# Rauchmelder.net
KiCad netlist of a schematic drawn in EAGLE
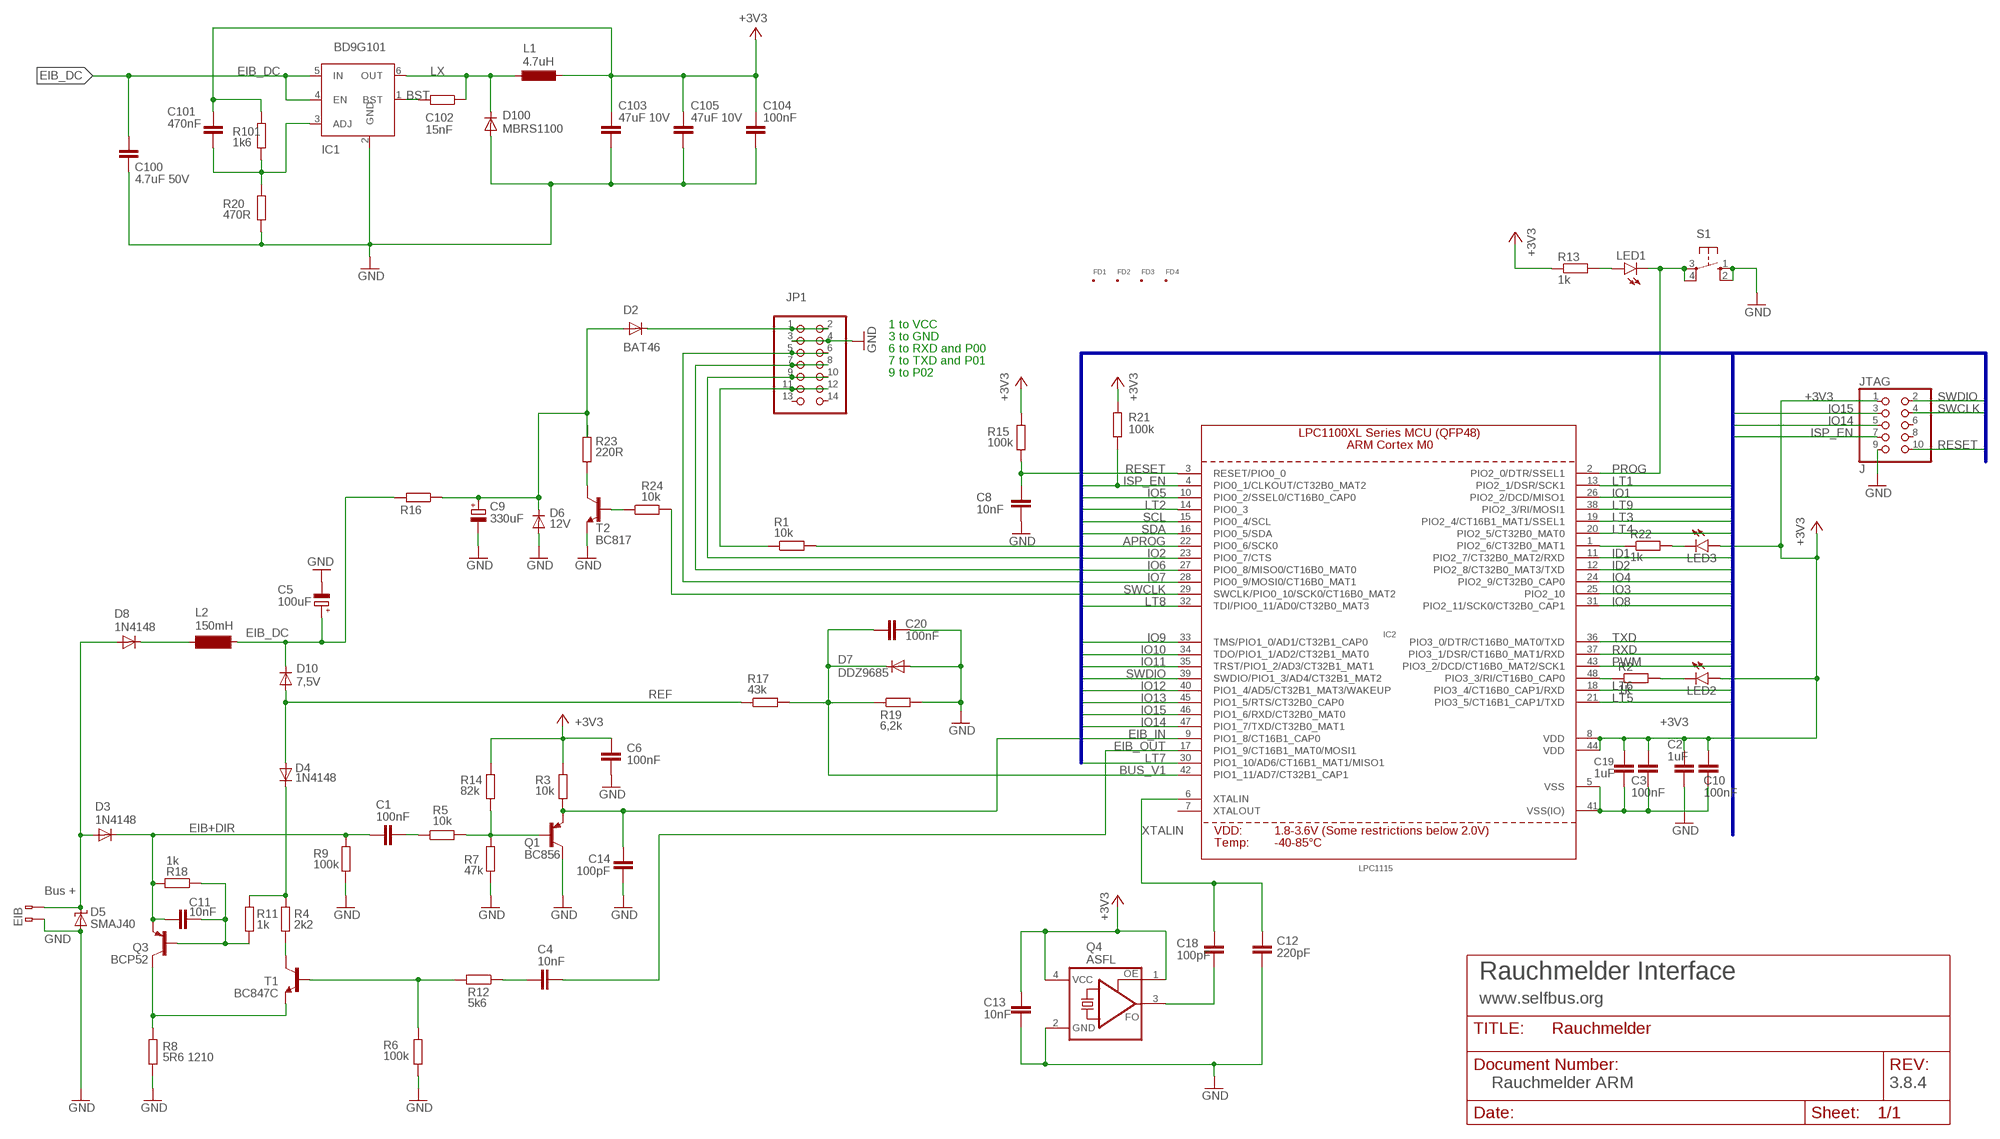
[diagram p0: schematic, sheet 1]

(export (version "E")
  (design (tool "Eeschema 10.0.6"))
  (components
    (comp (ref "C1")
      (value "100nF")
      (footprint "eagle-import:C0805")
      (libsource (lib "eagle-import") (part "C-EUC0805"))
    )
    (comp (ref "C2")
      (value "1uF")
      (footprint "eagle-import:C0805")
      (libsource (lib "eagle-import") (part "C-EUC0805"))
    )
    (comp (ref "C3")
      (value "100nF")
      (footprint "eagle-import:C0805")
      (libsource (lib "eagle-import") (part "C-EUC0805"))
    )
    (comp (ref "C4")
      (value "10nF")
      (footprint "eagle-import:C0805")
      (libsource (lib "eagle-import") (part "C-EUC0805"))
    )
    (comp (ref "C5")
      (value "100uF")
      (footprint "eagle-import:SANYO-OSCON_SMD_C6")
      (libsource (lib "eagle-import") (part "CPOL-EUSANYO_SMD_C6"))
    )
    (comp (ref "C6")
      (value "100nF")
      (footprint "eagle-import:C0805")
      (libsource (lib "eagle-import") (part "C-EUC0805"))
    )
    (comp (ref "C8")
      (value "10nF")
      (footprint "eagle-import:C0805")
      (libsource (lib "eagle-import") (part "C-EUC0805"))
    )
    (comp (ref "C9")
      (value "330uF")
      (footprint "eagle-import:E3,5-8")
      (libsource (lib "eagle-import") (part "CPOL-EUE3.5-8"))
    )
    (comp (ref "C10")
      (value "100nF")
      (footprint "eagle-import:C0805")
      (libsource (lib "eagle-import") (part "C-EUC0805"))
    )
    (comp (ref "C11")
      (value "10nF")
      (footprint "eagle-import:C0805")
      (libsource (lib "eagle-import") (part "C-EUC0805"))
    )
    (comp (ref "C12")
      (value "220pF")
      (footprint "eagle-import:C0805")
      (libsource (lib "eagle-import") (part "C-EUC0805"))
    )
    (comp (ref "C13")
      (value "10nF")
      (footprint "eagle-import:C0805")
      (libsource (lib "eagle-import") (part "C-EUC0805"))
    )
    (comp (ref "C14")
      (value "100pF")
      (footprint "eagle-import:C0805")
      (libsource (lib "eagle-import") (part "C-EUC0805"))
    )
    (comp (ref "C18")
      (value "100pF")
      (footprint "eagle-import:C0805")
      (libsource (lib "eagle-import") (part "C-EUC0805"))
    )
    (comp (ref "C19")
      (value "1uF")
      (footprint "eagle-import:C0805")
      (libsource (lib "eagle-import") (part "C-EUC0805"))
    )
    (comp (ref "C20")
      (value "100nF")
      (footprint "eagle-import:C0805")
      (libsource (lib "eagle-import") (part "C-EUC0805"))
    )
    (comp (ref "C100")
      (value "4.7uF 50V")
      (footprint "eagle-import:C0805")
      (libsource (lib "eagle-import") (part "C-EUC0805"))
    )
    (comp (ref "C101")
      (value "470nF")
      (footprint "eagle-import:C0805")
      (libsource (lib "eagle-import") (part "C-EUC0805"))
    )
    (comp (ref "C102")
      (value "15nF")
      (footprint "eagle-import:R0805")
      (libsource (lib "eagle-import") (part "R-EU_R0805"))
    )
    (comp (ref "C103")
      (value "47uF 10V")
      (footprint "eagle-import:C0805")
      (libsource (lib "eagle-import") (part "C-EUC0805"))
    )
    (comp (ref "C104")
      (value "100nF")
      (footprint "eagle-import:C0805")
      (libsource (lib "eagle-import") (part "C-EUC0805"))
    )
    (comp (ref "C105")
      (value "47uF 10V")
      (footprint "eagle-import:C0805")
      (libsource (lib "eagle-import") (part "C-EUC0805"))
    )
    (comp (ref "D2")
      (value "BAT46")
      (footprint "eagle-import:SOD-123")
      (libsource (lib "eagle-import") (part "DIODESOD-123"))
    )
    (comp (ref "D3")
      (value "1N4148")
      (footprint "eagle-import:SOD-123")
      (libsource (lib "eagle-import") (part "DIODESOD-123"))
    )
    (comp (ref "D4")
      (value "1N4148")
      (footprint "eagle-import:SOD-123")
      (libsource (lib "eagle-import") (part "DIODESOD-123"))
    )
    (comp (ref "D5")
      (value "SMAJ40")
      (footprint "eagle-import:SMBJ")
      (libsource (lib "eagle-import") (part "SUPPRESSOR-SMBJ"))
    )
    (comp (ref "D6")
      (value "12V")
      (footprint "eagle-import:SOD-123")
      (libsource (lib "eagle-import") (part "DIODESOD-123"))
    )
    (comp (ref "D7")
      (value "DDZ9685")
      (footprint "eagle-import:SOD-123")
      (libsource (lib "eagle-import") (part "DIODESOD-123"))
    )
    (comp (ref "D8")
      (value "1N4148")
      (footprint "eagle-import:SOD-123")
      (libsource (lib "eagle-import") (part "DIODESOD-123"))
    )
    (comp (ref "D10")
      (value "7,5V")
      (footprint "eagle-import:SOD-123")
      (libsource (lib "eagle-import") (part "DIODESOD-123"))
    )
    (comp (ref "D100")
      (value "MBRS1100")
      (footprint "eagle-import:SOD-123")
      (libsource (lib "eagle-import") (part "DIODESOD-123"))
    )
    (comp (ref "FD1")
      (value "FID_40MIL")
      (footprint "eagle-import:FID_040")
      (libsource (lib "eagle-import") (part "FID_40MIL"))
    )
    (comp (ref "FD2")
      (value "FID_40MIL")
      (footprint "eagle-import:FID_040")
      (libsource (lib "eagle-import") (part "FID_40MIL"))
    )
    (comp (ref "FD3")
      (value "FID_40MIL")
      (footprint "eagle-import:FID_040")
      (libsource (lib "eagle-import") (part "FID_40MIL"))
    )
    (comp (ref "FD4")
      (value "FID_40MIL")
      (footprint "eagle-import:FID_040")
      (libsource (lib "eagle-import") (part "FID_40MIL"))
    )
    (comp (ref "IC1")
      (value "BD9G101")
      (footprint "eagle-import:SOT23-6")
      (libsource (lib "eagle-import") (part "BD9G101GBD9G101G-SOT23-6"))
    )
    (comp (ref "IC2")
      (value "LPC1115")
      (footprint "eagle-import:LQFP48")
      (libsource (lib "eagle-import") (part "LPC1113/4/5_QFP48_XLSERIES"))
    )
    (comp (ref "JP1")
      (value "PINHD-2X7")
      (footprint "eagle-import:2X07")
      (libsource (lib "eagle-import") (part "PINHD-2X7"))
    )
    (comp (ref "JTAG")
      (value "J")
      (footprint "eagle-import:2X05M")
      (libsource (lib "eagle-import") (part "PINHD-2X05_2.00"))
    )
    (comp (ref "L1")
      (value "4.7uH")
      (footprint "eagle-import:L4532P")
      (libsource (lib "eagle-import") (part "L-EUL4532P"))
    )
    (comp (ref "L2")
      (value "150mH")
      (footprint "eagle-import:BS11")
      (libsource (lib "eagle-import") (part "BS11"))
    )
    (comp (ref "LED1")
      (value "LEDCHIPLED_0805")
      (footprint "eagle-import:CHIPLED_0805")
      (libsource (lib "eagle-import") (part "LEDCHIPLED_0805"))
    )
    (comp (ref "LED2")
      (value "LEDCHIPLED_0805")
      (footprint "eagle-import:CHIPLED_0805")
      (libsource (lib "eagle-import") (part "LEDCHIPLED_0805"))
    )
    (comp (ref "LED3")
      (value "LEDCHIPLED_0805")
      (footprint "eagle-import:CHIPLED_0805")
      (libsource (lib "eagle-import") (part "LEDCHIPLED_0805"))
    )
    (comp (ref "Q1")
      (value "BC856")
      (footprint "eagle-import:SOT23-BEC")
      (libsource (lib "eagle-import") (part "BC856SMDALT1"))
    )
    (comp (ref "Q3")
      (value "BCP52")
      (footprint "eagle-import:SOT223")
      (libsource (lib "eagle-import") (part "FZT753SMD"))
    )
    (comp (ref "Q4")
      (value "ASFL")
      (footprint "eagle-import:ASF")
      (fields (field (name "MPN") "ASFLM1-50.000MHZ-C-T"))
      (libsource (lib "eagle-import") (part "ASFL"))
    )
    (comp (ref "R1")
      (value "10k")
      (footprint "eagle-import:R0805")
      (libsource (lib "eagle-import") (part "R-EU_R0805"))
    )
    (comp (ref "R2")
      (value "1k")
      (footprint "eagle-import:R0805")
      (libsource (lib "eagle-import") (part "R-EU_R0805"))
    )
    (comp (ref "R3")
      (value "10k")
      (footprint "eagle-import:R0805")
      (libsource (lib "eagle-import") (part "R-EU_R0805"))
    )
    (comp (ref "R4")
      (value "2k2")
      (footprint "eagle-import:R0805")
      (libsource (lib "eagle-import") (part "R-EU_R0805"))
    )
    (comp (ref "R5")
      (value "10k")
      (footprint "eagle-import:R0805")
      (libsource (lib "eagle-import") (part "R-EU_R0805"))
    )
    (comp (ref "R6")
      (value "100k")
      (footprint "eagle-import:R0805")
      (libsource (lib "eagle-import") (part "R-EU_R0805"))
    )
    (comp (ref "R7")
      (value "47k")
      (footprint "eagle-import:R0805")
      (libsource (lib "eagle-import") (part "R-EU_R0805"))
    )
    (comp (ref "R8")
      (value "5R6 1210")
      (footprint "eagle-import:R1210")
      (libsource (lib "eagle-import") (part "R-EU_R1210"))
    )
    (comp (ref "R9")
      (value "100k")
      (footprint "eagle-import:R0805")
      (libsource (lib "eagle-import") (part "R-EU_R0805"))
    )
    (comp (ref "R11")
      (value "1k")
      (footprint "eagle-import:R0805")
      (libsource (lib "eagle-import") (part "R-EU_R0805"))
    )
    (comp (ref "R12")
      (value "5k6")
      (footprint "eagle-import:R0805")
      (libsource (lib "eagle-import") (part "R-EU_R0805"))
    )
    (comp (ref "R13")
      (value "1k")
      (footprint "eagle-import:R0805")
      (libsource (lib "eagle-import") (part "R-EU_R0805"))
    )
    (comp (ref "R14")
      (value "82k")
      (footprint "eagle-import:R0805")
      (libsource (lib "eagle-import") (part "R-EU_R0805"))
    )
    (comp (ref "R15")
      (value "100k")
      (footprint "eagle-import:R0805")
      (libsource (lib "eagle-import") (part "R-EU_R0805"))
    )
    (comp (ref "R16")
      (value "22k")
      (footprint "eagle-import:R0805")
      (libsource (lib "eagle-import") (part "R-EU_R0805"))
    )
    (comp (ref "R17")
      (value "43k")
      (footprint "eagle-import:R0805")
      (libsource (lib "eagle-import") (part "R-EU_R0805"))
    )
    (comp (ref "R18")
      (value "1k")
      (footprint "eagle-import:R0805")
      (libsource (lib "eagle-import") (part "R-EU_R0805"))
    )
    (comp (ref "R19")
      (value "6,2k")
      (footprint "eagle-import:R0805")
      (libsource (lib "eagle-import") (part "R-EU_R0805"))
    )
    (comp (ref "R20")
      (value "470R")
      (footprint "eagle-import:R0805")
      (libsource (lib "eagle-import") (part "R-EU_R0805"))
    )
    (comp (ref "R21")
      (value "100k")
      (footprint "eagle-import:R0805")
      (libsource (lib "eagle-import") (part "R-EU_R0805"))
    )
    (comp (ref "R22")
      (value "1k")
      (footprint "eagle-import:R0805")
      (libsource (lib "eagle-import") (part "R-EU_R0805"))
    )
    (comp (ref "R23")
      (value "220R")
      (footprint "eagle-import:R2512")
      (libsource (lib "eagle-import") (part "R-EU_R2512"))
    )
    (comp (ref "R24")
      (value "10k")
      (footprint "eagle-import:R0805")
      (libsource (lib "eagle-import") (part "R-EU_R0805"))
    )
    (comp (ref "R101")
      (value "1k6")
      (footprint "eagle-import:R0805")
      (libsource (lib "eagle-import") (part "R-EU_R0805"))
    )
    (comp (ref "S1")
      (value "10-XX")
      (footprint "eagle-import:B3F-10XX")
      (libsource (lib "eagle-import") (part "10-XX"))
    )
    (comp (ref "T1")
      (value "BC847C")
      (footprint "eagle-import:SOT23")
      (libsource (lib "eagle-import") (part "BC847C"))
    )
    (comp (ref "T2")
      (value "BC817")
      (footprint "eagle-import:SOT23-WIDE")
      (libsource (lib "eagle-import") (part "TRANSISTOR_NPNWIDE"))
    )
    (comp (ref "U$1")
      (value "EIB")
      (footprint "eagle-import:BUSKLEMME243-724")
      (libsource (lib "eagle-import") (part "EIB"))
    )
  )
  (nets
    (net (code "1") (name "+3V3") (class "Default")
      (node (ref "C10") (pin "2") (pinfunction "2_2") (pintype "passive"))
      (node (ref "C101") (pin "2") (pinfunction "2_2") (pintype "passive"))
      (node (ref "C103") (pin "1") (pinfunction "1_1") (pintype "passive"))
      (node (ref "C104") (pin "1") (pinfunction "1_1") (pintype "passive"))
      (node (ref "C105") (pin "1") (pinfunction "1_1") (pintype "passive"))
      (node (ref "C13") (pin "2") (pinfunction "2_2") (pintype "passive"))
      (node (ref "C19") (pin "2") (pinfunction "2_2") (pintype "passive"))
      (node (ref "C2") (pin "2") (pinfunction "2_2") (pintype "passive"))
      (node (ref "C3") (pin "2") (pinfunction "2_2") (pintype "passive"))
      (node (ref "C6") (pin "2") (pinfunction "2_2") (pintype "passive"))
      (node (ref "IC2") (pin "44") (pinfunction "VDD_44") (pintype "power_in"))
      (node (ref "IC2") (pin "8") (pinfunction "VDD_8") (pintype "power_in"))
      (node (ref "JTAG") (pin "1") (pinfunction "1_1") (pintype "passive"))
      (node (ref "L1") (pin "2") (pinfunction "2_2") (pintype "passive"))
      (node (ref "LED2") (pin "A") (pinfunction "A_A") (pintype "passive"))
      (node (ref "LED3") (pin "A") (pinfunction "A_A") (pintype "passive"))
      (node (ref "Q4") (pin "1") (pinfunction "OE_1") (pintype "input"))
      (node (ref "Q4") (pin "4") (pinfunction "VCC_4") (pintype "power_in"))
      (node (ref "R101") (pin "2") (pinfunction "2_2") (pintype "passive"))
      (node (ref "R13") (pin "1") (pinfunction "1_1") (pintype "passive"))
      (node (ref "R14") (pin "2") (pinfunction "2_2") (pintype "passive"))
      (node (ref "R15") (pin "1") (pinfunction "1_1") (pintype "passive"))
      (node (ref "R21") (pin "2") (pinfunction "2_2") (pintype "passive"))
      (node (ref "R3") (pin "2") (pinfunction "2_2") (pintype "passive"))
    )
    (net (code "2") (name "/APROG") (class "Default")
      (node (ref "IC2") (pin "22") (pinfunction "PIO0_6/SCK0_22") (pintype "bidirectional"))
    )
    (net (code "3") (name "/BST") (class "Default")
      (node (ref "C102") (pin "2") (pinfunction "2_2") (pintype "passive"))
      (node (ref "IC1") (pin "1") (pinfunction "BST_1") (pintype "output"))
    )
    (net (code "4") (name "/BUS_V1") (class "Default")
      (node (ref "C20") (pin "2") (pinfunction "2_2") (pintype "passive"))
      (node (ref "D7") (pin "C") (pinfunction "C_C") (pintype "passive"))
      (node (ref "IC2") (pin "42") (pinfunction "PIO1_11/AD7/CT32B1_CAP1_42") (pintype "bidirectional"))
      (node (ref "R17") (pin "2") (pinfunction "2_2") (pintype "passive"))
      (node (ref "R19") (pin "1") (pinfunction "1_1") (pintype "passive"))
    )
    (net (code "5") (name "/EIB+DIR") (class "Default")
      (node (ref "C1") (pin "1") (pinfunction "1_1") (pintype "passive"))
      (node (ref "C11") (pin "1") (pinfunction "1_1") (pintype "passive"))
      (node (ref "D3") (pin "C") (pinfunction "C_C") (pintype "passive"))
      (node (ref "Q3") (pin "3") (pinfunction "E_3") (pintype "passive"))
      (node (ref "R18") (pin "2") (pinfunction "2_2") (pintype "passive"))
      (node (ref "R9") (pin "2") (pinfunction "2_2") (pintype "passive"))
    )
    (net (code "6") (name "/EIB_IN") (class "Default")
      (node (ref "C14") (pin "2") (pinfunction "2_2") (pintype "passive"))
      (node (ref "IC2") (pin "9") (pinfunction "PIO1_8/CT16B1_CAP0_9") (pintype "bidirectional"))
      (node (ref "Q1") (pin "E") (pinfunction "E_E") (pintype "passive"))
      (node (ref "R3") (pin "1") (pinfunction "1_1") (pintype "passive"))
    )
    (net (code "7") (name "/EIB_OUT") (class "Default")
      (node (ref "C4") (pin "2") (pinfunction "2_2") (pintype "passive"))
      (node (ref "IC2") (pin "17") (pinfunction "PIO1_9/CT16B1_MAT0/MOSI1_17") (pintype "bidirectional"))
    )
    (net (code "8") (name "/ID1") (class "Default")
      (node (ref "IC2") (pin "11") (pinfunction "PIO2_7/CT32B0_MAT2/RXD_11") (pintype "bidirectional"))
    )
    (net (code "9") (name "/ID2") (class "Default")
      (node (ref "IC2") (pin "12") (pinfunction "PIO2_8/CT32B0_MAT3/TXD_12") (pintype "bidirectional"))
    )
    (net (code "10") (name "/IO1") (class "Default")
      (node (ref "IC2") (pin "26") (pinfunction "PIO2_2/DCD/MISO1_26") (pintype "bidirectional"))
    )
    (net (code "11") (name "/IO2") (class "Default")
      (node (ref "IC2") (pin "23") (pinfunction "PIO0_7/CTS_23") (pintype "bidirectional"))
    )
    (net (code "12") (name "/IO3") (class "Default")
      (node (ref "IC2") (pin "25") (pinfunction "PIO2_10_25") (pintype "bidirectional"))
    )
    (net (code "13") (name "/IO4") (class "Default")
      (node (ref "IC2") (pin "24") (pinfunction "PIO2_9/CT32B0_CAP0_24") (pintype "bidirectional"))
    )
    (net (code "14") (name "/IO5") (class "Default")
      (node (ref "IC2") (pin "10") (pinfunction "PIO0_2/SSEL0/CT16B0_CAP0_10") (pintype "bidirectional"))
    )
    (net (code "15") (name "/IO6") (class "Default")
      (node (ref "IC2") (pin "27") (pinfunction "PIO0_8/MISO0/CT16B0_MAT0_27") (pintype "bidirectional"))
    )
    (net (code "16") (name "/IO7") (class "Default")
      (node (ref "IC2") (pin "28") (pinfunction "PIO0_9/MOSI0/CT16B0_MAT1_28") (pintype "bidirectional"))
    )
    (net (code "17") (name "/IO8") (class "Default")
      (node (ref "IC2") (pin "31") (pinfunction "PIO2_11/SCK0/CT32B0_CAP1_31") (pintype "bidirectional"))
    )
    (net (code "18") (name "/IO9") (class "Default")
      (node (ref "IC2") (pin "33") (pinfunction "TMS/PIO1_0/AD1/CT32B1_CAP0_33") (pintype "bidirectional"))
    )
    (net (code "19") (name "/IO10") (class "Default")
      (node (ref "IC2") (pin "34") (pinfunction "TDO/PIO1_1/AD2/CT32B1_MAT0_34") (pintype "bidirectional"))
    )
    (net (code "20") (name "/IO11") (class "Default")
      (node (ref "IC2") (pin "35") (pinfunction "TRST/PIO1_2/AD3/CT32B1_MAT1_35") (pintype "bidirectional"))
    )
    (net (code "21") (name "/IO12") (class "Default")
      (node (ref "IC2") (pin "40") (pinfunction "PIO1_4/AD5/CT32B1_MAT3/WAKEUP_40") (pintype "bidirectional"))
    )
    (net (code "22") (name "/IO13") (class "Default")
      (node (ref "IC2") (pin "45") (pinfunction "PIO1_5/RTS/CT32B0_CAP0_45") (pintype "bidirectional"))
    )
    (net (code "23") (name "/IO14") (class "Default")
      (node (ref "IC2") (pin "47") (pinfunction "PIO1_7/TXD/CT32B0_MAT1_47") (pintype "bidirectional"))
      (node (ref "JTAG") (pin "5") (pinfunction "5_5") (pintype "passive"))
    )
    (net (code "24") (name "/IO15") (class "Default")
      (node (ref "IC2") (pin "46") (pinfunction "PIO1_6/RXD/CT32B0_MAT0_46") (pintype "bidirectional"))
      (node (ref "JTAG") (pin "3") (pinfunction "3_3") (pintype "passive"))
    )
    (net (code "25") (name "/ISP_EN") (class "Default")
      (node (ref "IC2") (pin "4") (pinfunction "PIO0_1/CLKOUT/CT32B0_MAT2_4") (pintype "bidirectional"))
      (node (ref "JTAG") (pin "7") (pinfunction "7_7") (pintype "passive"))
      (node (ref "R21") (pin "1") (pinfunction "1_1") (pintype "passive"))
    )
    (net (code "26") (name "/LT1") (class "Default")
      (node (ref "IC2") (pin "13") (pinfunction "PIO2_1/DSR/SCK1_13") (pintype "bidirectional"))
      (node (ref "R24") (pin "2") (pinfunction "2_2") (pintype "passive"))
    )
    (net (code "27") (name "/LT2") (class "Default")
      (node (ref "IC2") (pin "14") (pinfunction "PIO0_3_14") (pintype "bidirectional"))
    )
    (net (code "28") (name "/LT3") (class "Default")
      (node (ref "IC2") (pin "19") (pinfunction "PIO2_4/CT16B1_MAT1/SSEL1_19") (pintype "bidirectional"))
    )
    (net (code "29") (name "/LT4") (class "Default")
      (node (ref "IC2") (pin "20") (pinfunction "PIO2_5/CT32B0_MAT0_20") (pintype "bidirectional"))
    )
    (net (code "30") (name "/LT5") (class "Default")
      (node (ref "IC2") (pin "21") (pinfunction "PIO3_5/CT16B1_CAP1/TXD_21") (pintype "bidirectional"))
      (node (ref "JP1") (pin "10") (pinfunction "10_10") (pintype "passive"))
      (node (ref "JP1") (pin "9") (pinfunction "9_9") (pintype "passive"))
    )
    (net (code "31") (name "/LT6") (class "Default")
      (node (ref "IC2") (pin "18") (pinfunction "PIO3_4/CT16B0_CAP1/RXD_18") (pintype "bidirectional"))
    )
    (net (code "32") (name "/LT7") (class "Default")
      (node (ref "IC2") (pin "30") (pinfunction "PIO1_10/AD6/CT16B1_MAT1/MISO1_30") (pintype "bidirectional"))
    )
    (net (code "33") (name "/LT8") (class "Default")
      (node (ref "IC2") (pin "32") (pinfunction "TDI/PIO0_11/AD0/CT32B0_MAT3_32") (pintype "bidirectional"))
      (node (ref "R1") (pin "2") (pinfunction "2_2") (pintype "passive"))
    )
    (net (code "34") (name "/LT9") (class "Default")
      (node (ref "IC2") (pin "38") (pinfunction "PIO2_3/RI/MOSI1_38") (pintype "bidirectional"))
    )
    (net (code "35") (name "/LX") (class "Default")
      (node (ref "C102") (pin "1") (pinfunction "1_1") (pintype "passive"))
      (node (ref "D100") (pin "C") (pinfunction "C_C") (pintype "passive"))
      (node (ref "IC1") (pin "6") (pinfunction "OUT_6") (pintype "output"))
      (node (ref "L1") (pin "1") (pinfunction "1_1") (pintype "passive"))
    )
    (net (code "36") (name "/PROG") (class "Default")
      (node (ref "IC2") (pin "2") (pinfunction "PIO2_0/DTR/SSEL1_2") (pintype "bidirectional"))
      (node (ref "LED1") (pin "C") (pinfunction "C_C") (pintype "passive"))
      (node (ref "S1") (pin "3") (pinfunction "P_3") (pintype "passive"))
      (node (ref "S1") (pin "4") (pinfunction "P1_4") (pintype "passive"))
    )
    (net (code "37") (name "/PWM") (class "Default")
      (node (ref "IC2") (pin "43") (pinfunction "PIO3_2/DCD/CT16B0_MAT2/SCK1_43") (pintype "bidirectional"))
    )
    (net (code "38") (name "/REF") (class "Default")
      (node (ref "D10") (pin "A") (pinfunction "A_A") (pintype "passive"))
      (node (ref "D4") (pin "A") (pinfunction "A_A") (pintype "passive"))
      (node (ref "R17") (pin "1") (pinfunction "1_1") (pintype "passive"))
    )
    (net (code "39") (name "/RESET") (class "Default")
      (node (ref "C8") (pin "2") (pinfunction "2_2") (pintype "passive"))
      (node (ref "IC2") (pin "3") (pinfunction "RESET/PIO0_0_3") (pintype "bidirectional"))
      (node (ref "JTAG") (pin "10") (pinfunction "10_10") (pintype "passive"))
      (node (ref "R15") (pin "2") (pinfunction "2_2") (pintype "passive"))
    )
    (net (code "40") (name "/RXD") (class "Default")
      (node (ref "IC2") (pin "37") (pinfunction "PIO3_1/DSR/CT16B0_MAT1/RXD_37") (pintype "bidirectional"))
      (node (ref "JP1") (pin "5") (pinfunction "5_5") (pintype "passive"))
      (node (ref "JP1") (pin "6") (pinfunction "6_6") (pintype "passive"))
    )
    (net (code "41") (name "/SCL") (class "Default")
      (node (ref "IC2") (pin "15") (pinfunction "PIO0_4/SCL_15") (pintype "bidirectional"))
    )
    (net (code "42") (name "/SDA") (class "Default")
      (node (ref "IC2") (pin "16") (pinfunction "PIO0_5/SDA_16") (pintype "bidirectional"))
    )
    (net (code "43") (name "/SWCLK") (class "Default")
      (node (ref "IC2") (pin "29") (pinfunction "SWCLK/PIO0_10/SCK0/CT16B0_MAT2_29") (pintype "bidirectional"))
      (node (ref "JTAG") (pin "4") (pinfunction "4_4") (pintype "passive"))
    )
    (net (code "44") (name "/SWDIO") (class "Default")
      (node (ref "IC2") (pin "39") (pinfunction "SWDIO/PIO1_3/AD4/CT32B1_MAT2_39") (pintype "bidirectional"))
      (node (ref "JTAG") (pin "2") (pinfunction "2_2") (pintype "passive"))
    )
    (net (code "45") (name "/TXD") (class "Default")
      (node (ref "IC2") (pin "36") (pinfunction "PIO3_0/DTR/CT16B0_MAT0/TXD_36") (pintype "bidirectional"))
      (node (ref "JP1") (pin "7") (pinfunction "7_7") (pintype "passive"))
      (node (ref "JP1") (pin "8") (pinfunction "8_8") (pintype "passive"))
    )
    (net (code "46") (name "/XTALIN") (class "Default")
      (node (ref "C12") (pin "2") (pinfunction "2_2") (pintype "passive"))
      (node (ref "C18") (pin "2") (pinfunction "2_2") (pintype "passive"))
      (node (ref "IC2") (pin "6") (pinfunction "XTALIN_6") (pintype "input"))
    )
    (net (code "47") (name "EIB_DC") (class "Default")
      (node (ref "C100") (pin "2") (pinfunction "2_2") (pintype "passive"))
      (node (ref "C5") (pin "+") (pinfunction "+_+") (pintype "passive"))
      (node (ref "D10") (pin "C") (pinfunction "C_C") (pintype "passive"))
      (node (ref "IC1") (pin "4") (pinfunction "EN_4") (pintype "input"))
      (node (ref "IC1") (pin "5") (pinfunction "IN_5") (pintype "input"))
      (node (ref "L2") (pin "2") (pinfunction "2_2") (pintype "passive"))
      (node (ref "R16") (pin "2") (pinfunction "2_2") (pintype "passive"))
    )
    (net (code "48") (name "GND") (class "Default")
      (node (ref "C10") (pin "1") (pinfunction "1_1") (pintype "passive"))
      (node (ref "C100") (pin "1") (pinfunction "1_1") (pintype "passive"))
      (node (ref "C103") (pin "2") (pinfunction "2_2") (pintype "passive"))
      (node (ref "C104") (pin "2") (pinfunction "2_2") (pintype "passive"))
      (node (ref "C105") (pin "2") (pinfunction "2_2") (pintype "passive"))
      (node (ref "C12") (pin "1") (pinfunction "1_1") (pintype "passive"))
      (node (ref "C13") (pin "1") (pinfunction "1_1") (pintype "passive"))
      (node (ref "C14") (pin "1") (pinfunction "1_1") (pintype "passive"))
      (node (ref "C19") (pin "1") (pinfunction "1_1") (pintype "passive"))
      (node (ref "C2") (pin "1") (pinfunction "1_1") (pintype "passive"))
      (node (ref "C20") (pin "1") (pinfunction "1_1") (pintype "passive"))
      (node (ref "C3") (pin "1") (pinfunction "1_1") (pintype "passive"))
      (node (ref "C5") (pin "-") (pinfunction "-_-") (pintype "passive"))
      (node (ref "C6") (pin "1") (pinfunction "1_1") (pintype "passive"))
      (node (ref "C8") (pin "1") (pinfunction "1_1") (pintype "passive"))
      (node (ref "C9") (pin "-") (pinfunction "-_-") (pintype "passive"))
      (node (ref "D100") (pin "A") (pinfunction "A_A") (pintype "passive"))
      (node (ref "D5") (pin "A") (pinfunction "A_A") (pintype "passive"))
      (node (ref "D6") (pin "A") (pinfunction "A_A") (pintype "passive"))
      (node (ref "D7") (pin "A") (pinfunction "A_A") (pintype "passive"))
      (node (ref "IC1") (pin "2") (pinfunction "GND_2") (pintype "power_in"))
      (node (ref "IC2") (pin "41") (pinfunction "VSS(IO)_41") (pintype "power_in"))
      (node (ref "IC2") (pin "5") (pinfunction "VSS_5") (pintype "power_in"))
      (node (ref "JP1") (pin "3") (pinfunction "3_3") (pintype "passive"))
      (node (ref "JP1") (pin "4") (pinfunction "4_4") (pintype "passive"))
      (node (ref "JTAG") (pin "9") (pinfunction "9_9") (pintype "passive"))
      (node (ref "Q1") (pin "C") (pinfunction "C_C") (pintype "passive"))
      (node (ref "Q4") (pin "2") (pinfunction "GND_2") (pintype "power_in"))
      (node (ref "R19") (pin "2") (pinfunction "2_2") (pintype "passive"))
      (node (ref "R20") (pin "1") (pinfunction "1_1") (pintype "passive"))
      (node (ref "R6") (pin "1") (pinfunction "1_1") (pintype "passive"))
      (node (ref "R7") (pin "1") (pinfunction "1_1") (pintype "passive"))
      (node (ref "R8") (pin "1") (pinfunction "1_1") (pintype "passive"))
      (node (ref "R9") (pin "1") (pinfunction "1_1") (pintype "passive"))
      (node (ref "S1") (pin "1") (pinfunction "S_1") (pintype "passive"))
      (node (ref "S1") (pin "2") (pinfunction "S1_2") (pintype "passive"))
      (node (ref "T2") (pin "2") (pinfunction "E_2") (pintype "passive"))
      (node (ref "U$1") (pin "1") (pinfunction "B-1_1") (pintype "passive"))
    )
    (net (code "49") (name "Net-(C1-Pad2)") (class "Default")
      (node (ref "C1") (pin "2") (pinfunction "2_2") (pintype "passive"))
      (node (ref "R5") (pin "1") (pinfunction "1_1") (pintype "passive"))
    )
    (net (code "50") (name "Net-(C4-Pad1)") (class "Default")
      (node (ref "C4") (pin "1") (pinfunction "1_1") (pintype "passive"))
      (node (ref "R12") (pin "1") (pinfunction "1_1") (pintype "passive"))
    )
    (net (code "51") (name "Net-(C9-Pad+)") (class "Default")
      (node (ref "C9") (pin "+") (pinfunction "+_+") (pintype "passive"))
      (node (ref "D2") (pin "A") (pinfunction "A_A") (pintype "passive"))
      (node (ref "D6") (pin "C") (pinfunction "C_C") (pintype "passive"))
      (node (ref "R16") (pin "1") (pinfunction "1_1") (pintype "passive"))
      (node (ref "R23") (pin "1") (pinfunction "1_1") (pintype "passive"))
    )
    (net (code "52") (name "Net-(D2-PadC)") (class "Default")
      (node (ref "D2") (pin "C") (pinfunction "C_C") (pintype "passive"))
      (node (ref "JP1") (pin "1") (pinfunction "1_1") (pintype "passive"))
      (node (ref "JP1") (pin "2") (pinfunction "2_2") (pintype "passive"))
    )
    (net (code "53") (name "Net-(D4-PadC)") (class "Default")
      (node (ref "D4") (pin "C") (pinfunction "C_C") (pintype "passive"))
      (node (ref "R11") (pin "2") (pinfunction "2_2") (pintype "passive"))
      (node (ref "R4") (pin "2") (pinfunction "2_2") (pintype "passive"))
    )
    (net (code "54") (name "Net-(D8-PadC)") (class "Default")
      (node (ref "D8") (pin "C") (pinfunction "C_C") (pintype "passive"))
      (node (ref "L2") (pin "1") (pinfunction "1_1") (pintype "passive"))
    )
    (net (code "55") (name "Net-(IC1-ADJ)") (class "Default")
      (node (ref "C101") (pin "1") (pinfunction "1_1") (pintype "passive"))
      (node (ref "IC1") (pin "3") (pinfunction "ADJ_3") (pintype "passive"))
      (node (ref "R101") (pin "1") (pinfunction "1_1") (pintype "passive"))
      (node (ref "R20") (pin "2") (pinfunction "2_2") (pintype "passive"))
    )
    (net (code "56") (name "Net-(IC2-PIO2_6{slash}CT32B0_MAT1)") (class "Default")
      (node (ref "IC2") (pin "1") (pinfunction "PIO2_6/CT32B0_MAT1_1") (pintype "bidirectional"))
      (node (ref "R22") (pin "1") (pinfunction "1_1") (pintype "passive"))
    )
    (net (code "57") (name "Net-(IC2-PIO3_3{slash}RI{slash}CT16B0_CAP0)") (class "Default")
      (node (ref "IC2") (pin "48") (pinfunction "PIO3_3/RI/CT16B0_CAP0_48") (pintype "bidirectional"))
      (node (ref "R2") (pin "1") (pinfunction "1_1") (pintype "passive"))
    )
    (net (code "58") (name "Net-(JP1-Pad11)") (class "Default")
      (node (ref "JP1") (pin "11") (pinfunction "11_11") (pintype "passive"))
      (node (ref "JP1") (pin "12") (pinfunction "12_12") (pintype "passive"))
      (node (ref "R1") (pin "1") (pinfunction "1_1") (pintype "passive"))
    )
    (net (code "59") (name "Net-(LED1-PadA)") (class "Default")
      (node (ref "LED1") (pin "A") (pinfunction "A_A") (pintype "passive"))
      (node (ref "R13") (pin "2") (pinfunction "2_2") (pintype "passive"))
    )
    (net (code "60") (name "Net-(LED2-PadC)") (class "Default")
      (node (ref "LED2") (pin "C") (pinfunction "C_C") (pintype "passive"))
      (node (ref "R2") (pin "2") (pinfunction "2_2") (pintype "passive"))
    )
    (net (code "61") (name "Net-(LED3-PadC)") (class "Default")
      (node (ref "LED3") (pin "C") (pinfunction "C_C") (pintype "passive"))
      (node (ref "R22") (pin "2") (pinfunction "2_2") (pintype "passive"))
    )
    (net (code "62") (name "Net-(Q1-PadB)") (class "Default")
      (node (ref "Q1") (pin "B") (pinfunction "B_B") (pintype "passive"))
      (node (ref "R14") (pin "1") (pinfunction "1_1") (pintype "passive"))
      (node (ref "R5") (pin "2") (pinfunction "2_2") (pintype "passive"))
      (node (ref "R7") (pin "2") (pinfunction "2_2") (pintype "passive"))
    )
    (net (code "63") (name "Net-(Q3-B)") (class "Default")
      (node (ref "C11") (pin "2") (pinfunction "2_2") (pintype "passive"))
      (node (ref "Q3") (pin "1") (pinfunction "B_1") (pintype "passive"))
      (node (ref "R11") (pin "1") (pinfunction "1_1") (pintype "passive"))
      (node (ref "R18") (pin "1") (pinfunction "1_1") (pintype "passive"))
    )
    (net (code "64") (name "Net-(Q4-FO)") (class "Default")
      (node (ref "C18") (pin "1") (pinfunction "1_1") (pintype "passive"))
      (node (ref "Q4") (pin "3") (pinfunction "FO_3") (pintype "output"))
    )
    (net (code "65") (name "Net-(T1-B)") (class "Default")
      (node (ref "R12") (pin "2") (pinfunction "2_2") (pintype "passive"))
      (node (ref "R6") (pin "2") (pinfunction "2_2") (pintype "passive"))
      (node (ref "T1") (pin "1") (pinfunction "B_1") (pintype "passive"))
    )
    (net (code "66") (name "Net-(T1-C)") (class "Default")
      (node (ref "R4") (pin "1") (pinfunction "1_1") (pintype "passive"))
      (node (ref "T1") (pin "3") (pinfunction "C_3") (pintype "passive"))
    )
    (net (code "67") (name "Net-(T1-E)") (class "Default")
      (node (ref "Q3") (pin "2") (pinfunction "C_2") (pintype "passive"))
      (node (ref "Q3") (pin "4") (pinfunction "C_4") (pintype "passive"))
      (node (ref "R8") (pin "2") (pinfunction "2_2") (pintype "passive"))
      (node (ref "T1") (pin "2") (pinfunction "E_2") (pintype "passive"))
    )
    (net (code "68") (name "Net-(T2-B)") (class "Default")
      (node (ref "R24") (pin "1") (pinfunction "1_1") (pintype "passive"))
      (node (ref "T2") (pin "1") (pinfunction "B_1") (pintype "passive"))
    )
    (net (code "69") (name "Net-(T2-C)") (class "Default")
      (node (ref "R23") (pin "2") (pinfunction "2_2") (pintype "passive"))
      (node (ref "T2") (pin "3") (pinfunction "C_3") (pintype "passive"))
    )
    (net (code "70") (name "Net-(U$1-B-2)") (class "Default")
      (node (ref "D3") (pin "A") (pinfunction "A_A") (pintype "passive"))
      (node (ref "D5") (pin "C") (pinfunction "C_C") (pintype "passive"))
      (node (ref "D8") (pin "A") (pinfunction "A_A") (pintype "passive"))
      (node (ref "U$1") (pin "2") (pinfunction "B-2_2") (pintype "passive"))
    )
    (net (code "71") (name "unconnected-(IC2-XTALOUT-Pad7)") (class "Default")
      (node (ref "IC2") (pin "7") (pinfunction "XTALOUT_7") (pintype "output"))
    )
    (net (code "72") (name "unconnected-(JP1-Pad13)") (class "Default")
      (node (ref "JP1") (pin "13") (pinfunction "13_13") (pintype "passive"))
    )
    (net (code "73") (name "unconnected-(JP1-Pad14)") (class "Default")
      (node (ref "JP1") (pin "14") (pinfunction "14_14") (pintype "passive"))
    )
    (net (code "74") (name "unconnected-(JTAG-Pad6)") (class "Default")
      (node (ref "JTAG") (pin "6") (pinfunction "6_6") (pintype "passive"))
    )
    (net (code "75") (name "unconnected-(JTAG-Pad8)") (class "Default")
      (node (ref "JTAG") (pin "8") (pinfunction "8_8") (pintype "passive"))
    )
  )
)
